# no4_helloboard_syw.net
KiCad netlist of a schematic drawn in EAGLE
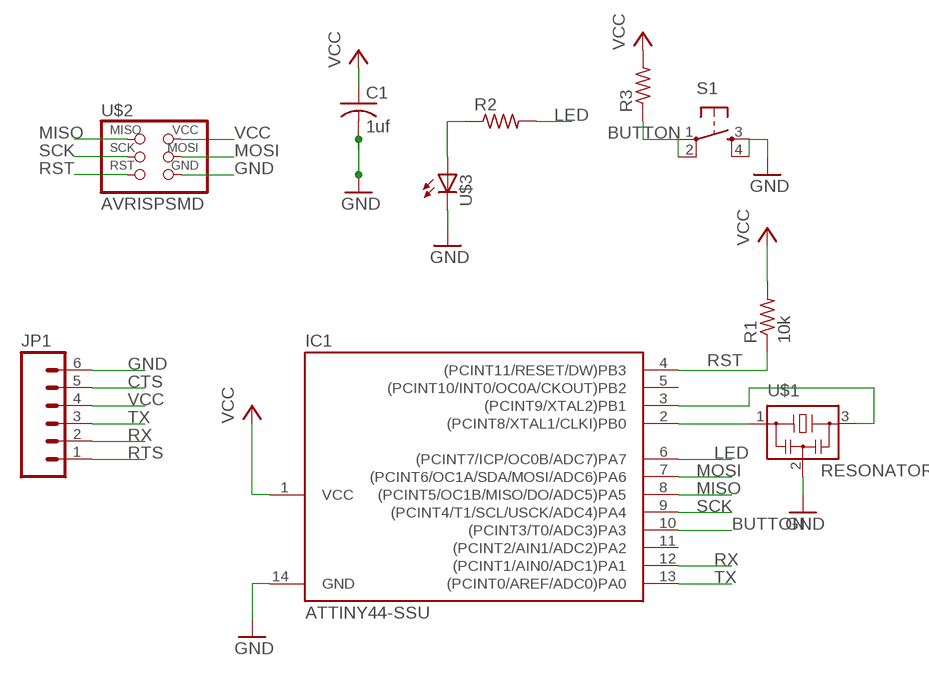
[diagram p0: schematic, sheet 1]

(export (version "E")
  (design (tool "Eeschema 10.0.6"))
  (components
    (comp (ref "C1")
      (value "1uf")
      (footprint "eagle-import:C1206")
      (libsource (lib "eagle-import") (part "C-USC1206"))
    )
    (comp (ref "IC1")
      (value "ATTINY44-SSU")
      (footprint "eagle-import:SOIC14")
      (libsource (lib "eagle-import") (part "ATTINY44-SSU"))
    )
    (comp (ref "JP1")
      (value "M06SMD")
      (footprint "eagle-import:1X06-SMD")
      (libsource (lib "eagle-import") (part "M06SMD"))
    )
    (comp (ref "R1")
      (value "10k")
      (footprint "eagle-import:R1206")
      (libsource (lib "eagle-import") (part "R-US_R1206"))
    )
    (comp (ref "R2")
      (value "RESISTOR1206")
      (footprint "eagle-import:1206")
      (libsource (lib "eagle-import") (part "RESISTOR1206"))
    )
    (comp (ref "R3")
      (value "RESISTOR1206")
      (footprint "eagle-import:1206")
      (libsource (lib "eagle-import") (part "RESISTOR1206"))
    )
    (comp (ref "S1")
      (value "6MM_SWITCH6MM_SWITCH")
      (footprint "eagle-import:6MM_SWITCH")
      (libsource (lib "eagle-import") (part "6MM_SWITCH6MM_SWITCH"))
    )
    (comp (ref "U$1")
      (value "RESONATOR")
      (footprint "eagle-import:EFOBM")
      (libsource (lib "eagle-import") (part "RESONATOR"))
    )
    (comp (ref "U$2")
      (value "AVRISPSMD")
      (footprint "eagle-import:2X03SMD")
      (libsource (lib "eagle-import") (part "AVRISPSMD"))
    )
    (comp (ref "U$3")
      (value "LED1206")
      (footprint "eagle-import:1206")
      (libsource (lib "eagle-import") (part "LED1206"))
    )
  )
  (nets
    (net (code "1") (name "/BUTTON") (class "Default")
      (node (ref "IC1") (pin "10") (pinfunction "(PCINT3/T0/ADC3)PA3_10") (pintype "bidirectional"))
      (node (ref "R3") (pin "1") (pinfunction "1_1") (pintype "passive"))
      (node (ref "S1") (pin "1") (pinfunction "P_1") (pintype "passive"))
      (node (ref "S1") (pin "2") (pinfunction "P1_2") (pintype "passive"))
    )
    (net (code "2") (name "/CTS") (class "Default")
      (node (ref "JP1") (pin "5") (pinfunction "5_5") (pintype "passive"))
    )
    (net (code "3") (name "/LED") (class "Default")
      (node (ref "IC1") (pin "6") (pinfunction "(PCINT7/ICP/OC0B/ADC7)PA7_6") (pintype "bidirectional"))
      (node (ref "R2") (pin "2") (pinfunction "2_2") (pintype "passive"))
    )
    (net (code "4") (name "/MISO") (class "Default")
      (node (ref "IC1") (pin "8") (pinfunction "(PCINT5/OC1B/MISO/DO/ADC5)PA5_8") (pintype "bidirectional"))
      (node (ref "U$2") (pin "1") (pinfunction "MISO_1") (pintype "passive"))
    )
    (net (code "5") (name "/MOSI") (class "Default")
      (node (ref "IC1") (pin "7") (pinfunction "(PCINT6/OC1A/SDA/MOSI/ADC6)PA6_7") (pintype "bidirectional"))
      (node (ref "U$2") (pin "4") (pinfunction "MOSI_4") (pintype "passive"))
    )
    (net (code "6") (name "/RST") (class "Default")
      (node (ref "IC1") (pin "4") (pinfunction "(PCINT11/RESET/DW)PB3_4") (pintype "bidirectional"))
      (node (ref "R1") (pin "1") (pinfunction "1_1") (pintype "passive"))
      (node (ref "U$2") (pin "5") (pinfunction "RST_5") (pintype "passive"))
    )
    (net (code "7") (name "/RTS") (class "Default")
      (node (ref "JP1") (pin "1") (pinfunction "1_1") (pintype "passive"))
    )
    (net (code "8") (name "/RX") (class "Default")
      (node (ref "IC1") (pin "12") (pinfunction "(PCINT1/AIN0/ADC1)PA1_12") (pintype "bidirectional"))
      (node (ref "JP1") (pin "2") (pinfunction "2_2") (pintype "passive"))
    )
    (net (code "9") (name "/SCK") (class "Default")
      (node (ref "IC1") (pin "9") (pinfunction "(PCINT4/T1/SCL/USCK/ADC4)PA4_9") (pintype "bidirectional"))
      (node (ref "U$2") (pin "3") (pinfunction "SCK_3") (pintype "passive"))
    )
    (net (code "10") (name "/TX") (class "Default")
      (node (ref "IC1") (pin "13") (pinfunction "(PCINT0/AREF/ADC0)PA0_13") (pintype "bidirectional"))
      (node (ref "JP1") (pin "3") (pinfunction "3_3") (pintype "passive"))
    )
    (net (code "11") (name "GND") (class "Default")
      (node (ref "C1") (pin "2") (pinfunction "2_2") (pintype "passive"))
      (node (ref "IC1") (pin "14") (pinfunction "GND_14") (pintype "power_in"))
      (node (ref "JP1") (pin "6") (pinfunction "6_6") (pintype "passive"))
      (node (ref "S1") (pin "3") (pinfunction "S_3") (pintype "passive"))
      (node (ref "S1") (pin "4") (pinfunction "S1_4") (pintype "passive"))
      (node (ref "U$1") (pin "2") (pinfunction "2_2") (pintype "passive"))
      (node (ref "U$2") (pin "6") (pinfunction "GND_6") (pintype "passive"))
      (node (ref "U$3") (pin "2") (pinfunction "C_2") (pintype "passive"))
    )
    (net (code "12") (name "Net-(IC1-(PCINT8{slash}XTAL1{slash}CLKI)PB0)") (class "Default")
      (node (ref "IC1") (pin "2") (pinfunction "(PCINT8/XTAL1/CLKI)PB0_2") (pintype "bidirectional"))
      (node (ref "U$1") (pin "1") (pinfunction "1_1") (pintype "passive"))
    )
    (net (code "13") (name "Net-(IC1-(PCINT9{slash}XTAL2)PB1)") (class "Default")
      (node (ref "IC1") (pin "3") (pinfunction "(PCINT9/XTAL2)PB1_3") (pintype "bidirectional"))
      (node (ref "U$1") (pin "3") (pinfunction "3_3") (pintype "passive"))
    )
    (net (code "14") (name "Net-(U$3-A)") (class "Default")
      (node (ref "R2") (pin "1") (pinfunction "1_1") (pintype "passive"))
      (node (ref "U$3") (pin "1") (pinfunction "A_1") (pintype "passive"))
    )
    (net (code "15") (name "VCC") (class "Default")
      (node (ref "C1") (pin "1") (pinfunction "1_1") (pintype "passive"))
      (node (ref "IC1") (pin "1") (pinfunction "VCC_1") (pintype "power_in"))
      (node (ref "JP1") (pin "4") (pinfunction "4_4") (pintype "passive"))
      (node (ref "R1") (pin "2") (pinfunction "2_2") (pintype "passive"))
      (node (ref "R3") (pin "2") (pinfunction "2_2") (pintype "passive"))
      (node (ref "U$2") (pin "2") (pinfunction "VCC_2") (pintype "passive"))
    )
    (net (code "16") (name "unconnected-(IC1-(PCINT2{slash}AIN1{slash}ADC2)PA2-Pad11)") (class "Default")
      (node (ref "IC1") (pin "11") (pinfunction "(PCINT2/AIN1/ADC2)PA2_11") (pintype "bidirectional"))
    )
    (net (code "17") (name "unconnected-(IC1-(PCINT10{slash}INT0{slash}OC0A{slash}CKOUT)PB2-Pad5)") (class "Default")
      (node (ref "IC1") (pin "5") (pinfunction "(PCINT10/INT0/OC0A/CKOUT)PB2_5") (pintype "bidirectional"))
    )
  )
)
